# CAN_Sheet.net
KiCad netlist of a schematic drawn in Altium Designer
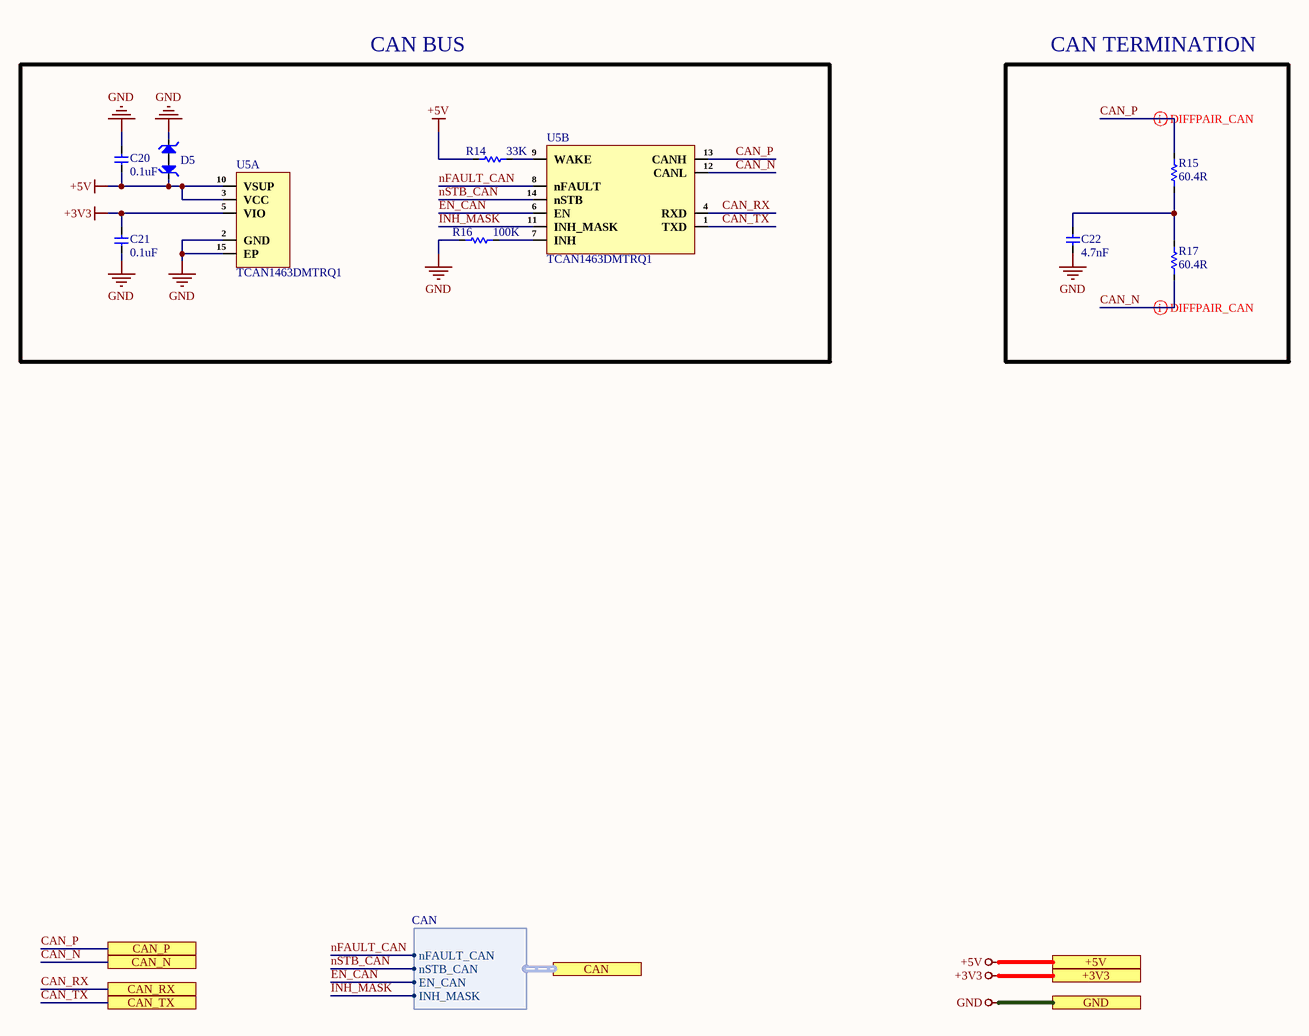
[diagram p0: CAN_Sheet.SchDoc]

(export (version "E")
  (design (tool "Eeschema 10.0.6"))
  (components
    (comp (ref "C20")
      (value "0.1uF")
      (footprint "Cap-0402")
      (description "CAP CER 0.1UF 16V X7R 0402")
      (fields
        (field (name "MANUFACTURER") "Yageo")
        (field (name "MANUFACTURER PART NUMBER") "CC0402JRX7R7BB104")
      )
      (libsource (lib "eSpark Libraries") (part "CC0402JRX7R7BB104"))
    )
    (comp (ref "C21")
      (value "0.1uF")
      (footprint "Cap-0402")
      (description "CAP CER 0.1UF 16V X7R 0402")
      (fields
        (field (name "MANUFACTURER") "Yageo")
        (field (name "MANUFACTURER PART NUMBER") "CC0402JRX7R7BB104")
      )
      (libsource (lib "eSpark Libraries") (part "CC0402JRX7R7BB104"))
    )
    (comp (ref "C22")
      (value "4.7nF")
      (footprint "Cap-0402")
      (description "CAP CER 4700PF 50V X7R 0402")
      (fields
        (field (name "MANUFACTURER") "Yageo")
        (field (name "MANUFACTURER PART NUMBER") "CC0402KRX7R9BB472")
      )
      (libsource (lib "eSpark Libraries") (part "CC0402KRX7R9BB472"))
    )
    (comp (ref "D5")
      (value "PESD5V0H1BSFYL")
      (footprint "DSN0603-2")
      (description "TVS DIODE 5VWM 6.3VC DSN0603-2")
      (fields (field (name "MANUFACTURER") "Nexperia") (field (name "LCSC PART NUMBER") "C477989"))
      (libsource (lib "eSpark Libraries") (part "PESD5V0H1BSFYL"))
    )
    (comp (ref "R14")
      (value "33K")
      (footprint "Res-0402")
      (description "RES 33K OHM 1% 1/16W 0402")
      (fields
        (field (name "MANUFACTURER") "YAGEO")
        (field (name "MANUFACTURER PART NUMBER") "RC0402FR-0733KL")
      )
      (libsource (lib "eSpark Libraries") (part "RC0402FR-0733KL"))
    )
    (comp (ref "R15")
      (value "60.4R")
      (footprint "Res-0603")
      (description "100mW Thick Film Resistors ±100ppm/℃ ±1% 60.4Ω 0603 Chip Resistor - Surface Mount ROHS")
      (fields
        (field (name "MANUFACTURER PART NUMBER") "RTT0360R4FTP")
        (field (name "LCSC PART NUMBER") "C103744")
      )
      (libsource (lib "eSpark Libraries") (part "RTT0360R4FTP"))
    )
    (comp (ref "R16")
      (value "100K")
      (footprint "Res-0402")
      (description "RES 100K OHM 1% 1/16W 0402")
      (fields
        (field (name "MANUFACTURER") "Yageo")
        (field (name "MANUFACTURER PART NUMBER") "RC0402FR-07100KL")
      )
      (libsource (lib "eSpark Libraries") (part "RC0402FR-07100KL"))
    )
    (comp (ref "R17")
      (value "60.4R")
      (footprint "Res-0603")
      (description "100mW Thick Film Resistors ±100ppm/℃ ±1% 60.4Ω 0603 Chip Resistor - Surface Mount ROHS")
      (fields
        (field (name "MANUFACTURER PART NUMBER") "RTT0360R4FTP")
        (field (name "LCSC PART NUMBER") "C103744")
      )
      (libsource (lib "eSpark Libraries") (part "RTT0360R4FTP"))
    )
    (comp (ref "U5")
      (value "TCAN1463DMTRQ1")
      (footprint "VSON-14(3x4.5)")
      (description "IC TRANSCEIVER HALF 1/1 14VSON")
      (fields (field (name "MANUFACTURER") "Texas Instruments") (field (name "LCSC PART NUMBER") "C5215823"))
      (libsource (lib "eSpark Libraries") (part "TCAN1463DMTRQ1"))
    )
  )
  (nets
    (net (code "2") (name "+3V3") (class "Default")
      (node (ref "C21") (pin "2") (pinfunction "2_2") (pintype "passive"))
      (node (ref "U5") (pin "5") (pinfunction "VIO_5") (pintype "passive"))
    )
    (net (code "3") (name "+5V") (class "Default")
      (node (ref "C20") (pin "1") (pinfunction "1_1") (pintype "passive"))
      (node (ref "D5") (pin "1") (pinfunction "1_1") (pintype "passive"))
      (node (ref "R14") (pin "1") (pinfunction "1_1") (pintype "passive"))
      (node (ref "U5") (pin "10") (pinfunction "VSUP_10") (pintype "passive"))
      (node (ref "U5") (pin "3") (pinfunction "VCC_3") (pintype "passive"))
    )
    (net (code "4") (name "/CAN_N") (class "Default")
      (node (ref "R17") (pin "2") (pinfunction "2_2") (pintype "passive"))
      (node (ref "U5") (pin "12") (pinfunction "CANL_12") (pintype "passive"))
    )
    (net (code "5") (name "/CAN_P") (class "Default")
      (node (ref "R15") (pin "1") (pinfunction "1_1") (pintype "passive"))
      (node (ref "U5") (pin "13") (pinfunction "CANH_13") (pintype "passive"))
    )
    (net (code "6") (name "/CAN_RX") (class "Default")
      (node (ref "U5") (pin "4") (pinfunction "RXD_4") (pintype "passive"))
    )
    (net (code "7") (name "/CAN_TX") (class "Default")
      (node (ref "U5") (pin "1") (pinfunction "TXD_1") (pintype "passive"))
    )
    (net (code "8") (name "/EN_CAN") (class "Default")
      (node (ref "U5") (pin "6") (pinfunction "EN_6") (pintype "passive"))
    )
    (net (code "9") (name "/INH_MASK") (class "Default")
      (node (ref "U5") (pin "11") (pinfunction "INH_MASK_11") (pintype "passive"))
    )
    (net (code "10") (name "/nFAULT_CAN") (class "Default")
      (node (ref "U5") (pin "8") (pinfunction "nFAULT_8") (pintype "passive"))
    )
    (net (code "11") (name "/nSTB_CAN") (class "Default")
      (node (ref "U5") (pin "14") (pinfunction "nSTB_14") (pintype "passive"))
    )
    (net (code "13") (name "GND") (class "Default")
      (node (ref "C20") (pin "2") (pinfunction "2_2") (pintype "passive"))
      (node (ref "C21") (pin "1") (pinfunction "1_1") (pintype "passive"))
      (node (ref "C22") (pin "2") (pinfunction "2_2") (pintype "passive"))
      (node (ref "D5") (pin "2") (pinfunction "2_2") (pintype "passive"))
      (node (ref "R16") (pin "1") (pinfunction "1_1") (pintype "passive"))
      (node (ref "U5") (pin "15") (pinfunction "EP_15") (pintype "passive"))
      (node (ref "U5") (pin "2") (pinfunction "GND_2") (pintype "passive"))
    )
    (net (code "14") (name "Net-(C22-Pad1)") (class "Default")
      (node (ref "C22") (pin "1") (pinfunction "1_1") (pintype "passive"))
      (node (ref "R15") (pin "2") (pinfunction "2_2") (pintype "passive"))
      (node (ref "R17") (pin "1") (pinfunction "1_1") (pintype "passive"))
    )
    (net (code "15") (name "Net-(U5B-INH)") (class "Default")
      (node (ref "R16") (pin "2") (pinfunction "2_2") (pintype "passive"))
      (node (ref "U5") (pin "7") (pinfunction "INH_7") (pintype "passive"))
    )
    (net (code "16") (name "Net-(U5B-WAKE)") (class "Default")
      (node (ref "R14") (pin "2") (pinfunction "2_2") (pintype "passive"))
      (node (ref "U5") (pin "9") (pinfunction "WAKE_9") (pintype "passive"))
    )
  )
)
